# simple_eq_5532.net
KiCad netlist of a schematic drawn in EAGLE
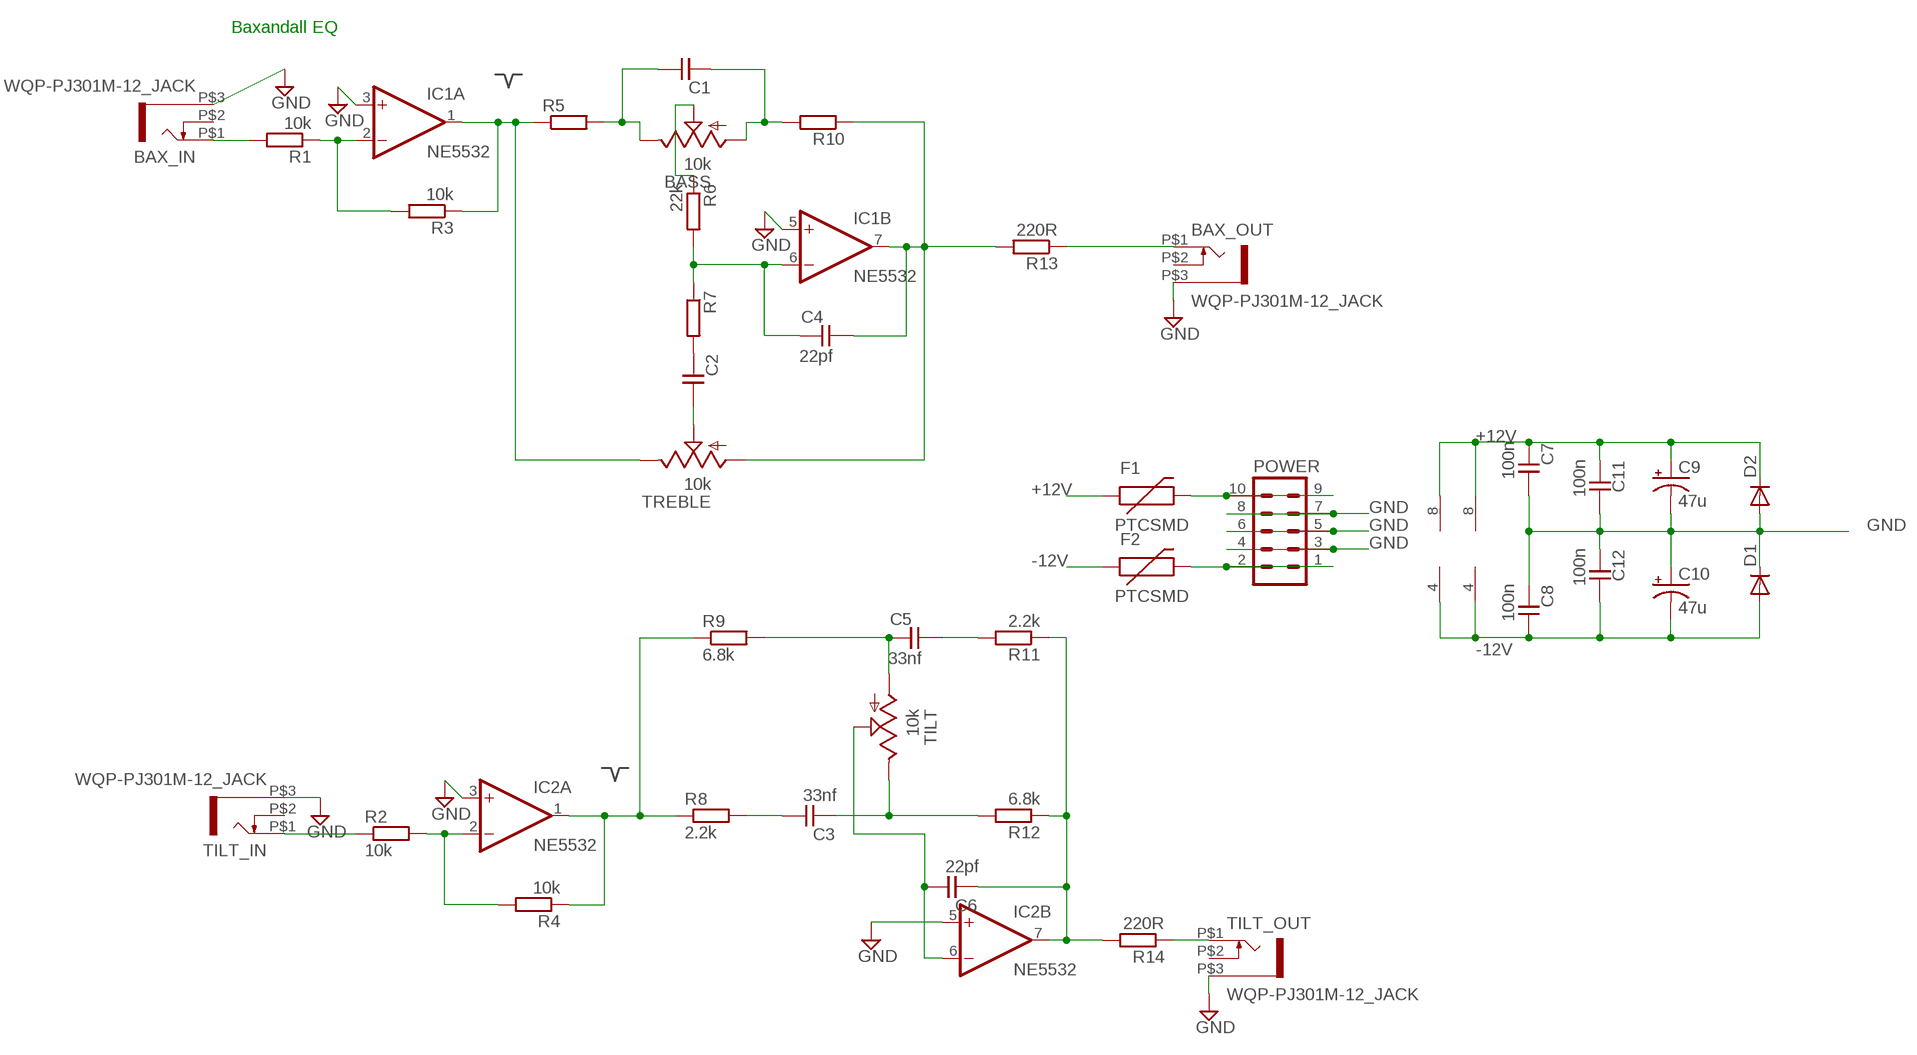
[diagram p0: schematic, sheet 1]

(export (version "E")
  (design (tool "Eeschema 10.0.6"))
  (components
    (comp (ref "BASS")
      (value "10k")
      (footprint "eagle-import:EVUF")
      (libsource (lib "eagle-import") (part "ALPHA-9MMAF2"))
    )
    (comp (ref "BAX_IN")
      (value "WQP-PJ301M-12_JACK")
      (footprint "eagle-import:WQP-PJ301M-12_JACK")
      (libsource (lib "eagle-import") (part "WQP-PJ301M-12_JACK"))
    )
    (comp (ref "BAX_OUT")
      (value "WQP-PJ301M-12_JACK")
      (footprint "eagle-import:WQP-PJ301M-12_JACK")
      (libsource (lib "eagle-import") (part "WQP-PJ301M-12_JACK"))
    )
    (comp (ref "C1")
      (value "C-EU0805_CAP")
      (footprint "eagle-import:R0805")
      (libsource (lib "eagle-import") (part "C-EU0805_CAP"))
    )
    (comp (ref "C2")
      (value "C-EU0805_CAP")
      (footprint "eagle-import:R0805")
      (libsource (lib "eagle-import") (part "C-EU0805_CAP"))
    )
    (comp (ref "C3")
      (value "33nf")
      (footprint "eagle-import:R0805")
      (libsource (lib "eagle-import") (part "C-EU0805_CAP"))
    )
    (comp (ref "C4")
      (value "22pf")
      (footprint "eagle-import:R0805")
      (libsource (lib "eagle-import") (part "C-EU0805_CAP"))
    )
    (comp (ref "C5")
      (value "33nf")
      (footprint "eagle-import:R0805")
      (libsource (lib "eagle-import") (part "C-EU0805_CAP"))
    )
    (comp (ref "C6")
      (value "22pf")
      (footprint "eagle-import:R0805")
      (libsource (lib "eagle-import") (part "C-EU0805_CAP"))
    )
    (comp (ref "C7")
      (value "100n")
      (footprint "eagle-import:R0805")
      (libsource (lib "eagle-import") (part "C-EU0805_CAP"))
    )
    (comp (ref "C8")
      (value "100n")
      (footprint "eagle-import:R0805")
      (libsource (lib "eagle-import") (part "C-EU0805_CAP"))
    )
    (comp (ref "C9")
      (value "47u")
      (footprint "eagle-import:PANASONIC_D")
      (libsource (lib "eagle-import") (part "CPOL-USD"))
    )
    (comp (ref "C10")
      (value "47u")
      (footprint "eagle-import:PANASONIC_D")
      (libsource (lib "eagle-import") (part "CPOL-USD"))
    )
    (comp (ref "C11")
      (value "100n")
      (footprint "eagle-import:R0805")
      (libsource (lib "eagle-import") (part "C-EU0805_CAP"))
    )
    (comp (ref "C12")
      (value "100n")
      (footprint "eagle-import:R0805")
      (libsource (lib "eagle-import") (part "C-EU0805_CAP"))
    )
    (comp (ref "D1")
      (value "DIODE-SOD123")
      (footprint "eagle-import:SOD123")
      (libsource (lib "eagle-import") (part "DIODE-SOD123"))
    )
    (comp (ref "D2")
      (value "DIODE-SOD123")
      (footprint "eagle-import:SOD123")
      (libsource (lib "eagle-import") (part "DIODE-SOD123"))
    )
    (comp (ref "F1")
      (value "PTCSMD")
      (footprint "eagle-import:PTC-1206")
      (libsource (lib "eagle-import") (part "PTCSMD"))
    )
    (comp (ref "F2")
      (value "PTCSMD")
      (footprint "eagle-import:PTC-1206")
      (libsource (lib "eagle-import") (part "PTCSMD"))
    )
    (comp (ref "IC1")
      (value "NE5532")
      (footprint "eagle-import:SO08")
      (libsource (lib "eagle-import") (part "TL072D"))
    )
    (comp (ref "IC2")
      (value "NE5532")
      (footprint "eagle-import:SO08")
      (libsource (lib "eagle-import") (part "TL072D"))
    )
    (comp (ref "POWER")
      (value "10_PIN_HEADER")
      (footprint "eagle-import:MA05-2")
      (libsource (lib "eagle-import") (part "10_PIN_HEADER"))
    )
    (comp (ref "R1")
      (value "10k")
      (footprint "eagle-import:R0805")
      (libsource (lib "eagle-import") (part "R-EU_R0805"))
    )
    (comp (ref "R2")
      (value "10k")
      (footprint "eagle-import:R0805")
      (libsource (lib "eagle-import") (part "R-EU_R0805"))
    )
    (comp (ref "R3")
      (value "10k")
      (footprint "eagle-import:R0805")
      (libsource (lib "eagle-import") (part "R-EU_R0805"))
    )
    (comp (ref "R4")
      (value "10k")
      (footprint "eagle-import:R0805")
      (libsource (lib "eagle-import") (part "R-EU_R0805"))
    )
    (comp (ref "R5")
      (value "R-EU_R0805")
      (footprint "eagle-import:R0805")
      (libsource (lib "eagle-import") (part "R-EU_R0805"))
    )
    (comp (ref "R6")
      (value "22k")
      (footprint "eagle-import:R0805")
      (libsource (lib "eagle-import") (part "R-EU_R0805"))
    )
    (comp (ref "R7")
      (value "R-EU_R0805")
      (footprint "eagle-import:R0805")
      (libsource (lib "eagle-import") (part "R-EU_R0805"))
    )
    (comp (ref "R8")
      (value "2.2k")
      (footprint "eagle-import:R0805")
      (libsource (lib "eagle-import") (part "R-EU_R0805"))
    )
    (comp (ref "R9")
      (value "6.8k")
      (footprint "eagle-import:R0805")
      (libsource (lib "eagle-import") (part "R-EU_R0805"))
    )
    (comp (ref "R10")
      (value "R-EU_R0805")
      (footprint "eagle-import:R0805")
      (libsource (lib "eagle-import") (part "R-EU_R0805"))
    )
    (comp (ref "R11")
      (value "2.2k")
      (footprint "eagle-import:R0805")
      (libsource (lib "eagle-import") (part "R-EU_R0805"))
    )
    (comp (ref "R12")
      (value "6.8k")
      (footprint "eagle-import:R0805")
      (libsource (lib "eagle-import") (part "R-EU_R0805"))
    )
    (comp (ref "R13")
      (value "220R")
      (footprint "eagle-import:R0805")
      (libsource (lib "eagle-import") (part "R-EU_R0805"))
    )
    (comp (ref "R14")
      (value "220R")
      (footprint "eagle-import:R0805")
      (libsource (lib "eagle-import") (part "R-EU_R0805"))
    )
    (comp (ref "TILT")
      (value "10k")
      (footprint "eagle-import:EVUF")
      (libsource (lib "eagle-import") (part "ALPHA-9MMAF2"))
    )
    (comp (ref "TILT_IN")
      (value "WQP-PJ301M-12_JACK")
      (footprint "eagle-import:WQP-PJ301M-12_JACK")
      (libsource (lib "eagle-import") (part "WQP-PJ301M-12_JACK"))
    )
    (comp (ref "TILT_OUT")
      (value "WQP-PJ301M-12_JACK")
      (footprint "eagle-import:WQP-PJ301M-12_JACK")
      (libsource (lib "eagle-import") (part "WQP-PJ301M-12_JACK"))
    )
    (comp (ref "TREBLE")
      (value "10k")
      (footprint "eagle-import:EVUF")
      (libsource (lib "eagle-import") (part "ALPHA-9MMAF2"))
    )
  )
  (nets
    (net (code "1") (name "/+12V") (class "Default")
      (node (ref "C11") (pin "2") (pinfunction "2_2") (pintype "passive"))
      (node (ref "C7") (pin "2") (pinfunction "2_2") (pintype "passive"))
      (node (ref "C9") (pin "+") (pinfunction "+_+") (pintype "passive"))
      (node (ref "D2") (pin "C") (pinfunction "C_C") (pintype "passive"))
      (node (ref "F1") (pin "1") (pinfunction "1_1") (pintype "bidirectional"))
      (node (ref "IC1") (pin "8") (pinfunction "V+_8") (pintype "power_in"))
      (node (ref "IC2") (pin "8") (pinfunction "V+_8") (pintype "power_in"))
    )
    (net (code "2") (name "/-12V") (class "Default")
      (node (ref "C10") (pin "-") (pinfunction "-_-") (pintype "passive"))
      (node (ref "C12") (pin "1") (pinfunction "1_1") (pintype "passive"))
      (node (ref "C8") (pin "1") (pinfunction "1_1") (pintype "passive"))
      (node (ref "D1") (pin "A") (pinfunction "A_A") (pintype "passive"))
      (node (ref "F2") (pin "1") (pinfunction "1_1") (pintype "bidirectional"))
      (node (ref "IC1") (pin "4") (pinfunction "V-_4") (pintype "power_in"))
      (node (ref "IC2") (pin "4") (pinfunction "V-_4") (pintype "power_in"))
    )
    (net (code "3") (name "GND") (class "Default")
      (node (ref "BAX_IN") (pin "P$3") (pinfunction "1_P$3") (pintype "passive"))
      (node (ref "BAX_OUT") (pin "P$3") (pinfunction "1_P$3") (pintype "passive"))
      (node (ref "C10") (pin "+") (pinfunction "+_+") (pintype "passive"))
      (node (ref "C11") (pin "1") (pinfunction "1_1") (pintype "passive"))
      (node (ref "C12") (pin "2") (pinfunction "2_2") (pintype "passive"))
      (node (ref "C7") (pin "1") (pinfunction "1_1") (pintype "passive"))
      (node (ref "C8") (pin "2") (pinfunction "2_2") (pintype "passive"))
      (node (ref "C9") (pin "-") (pinfunction "-_-") (pintype "passive"))
      (node (ref "D1") (pin "C") (pinfunction "C_C") (pintype "passive"))
      (node (ref "D2") (pin "A") (pinfunction "A_A") (pintype "passive"))
      (node (ref "IC1") (pin "3") (pinfunction "+IN_3") (pintype "input"))
      (node (ref "IC1") (pin "5") (pinfunction "+IN_5") (pintype "input"))
      (node (ref "IC2") (pin "3") (pinfunction "+IN_3") (pintype "input"))
      (node (ref "IC2") (pin "5") (pinfunction "+IN_5") (pintype "input"))
      (node (ref "POWER") (pin "3") (pinfunction "3_3") (pintype "passive"))
      (node (ref "POWER") (pin "4") (pinfunction "4_4") (pintype "passive"))
      (node (ref "POWER") (pin "5") (pinfunction "5_5") (pintype "passive"))
      (node (ref "POWER") (pin "6") (pinfunction "6_6") (pintype "passive"))
      (node (ref "POWER") (pin "7") (pinfunction "7_7") (pintype "passive"))
      (node (ref "POWER") (pin "8") (pinfunction "8_8") (pintype "passive"))
      (node (ref "TILT_IN") (pin "P$3") (pinfunction "1_P$3") (pintype "passive"))
      (node (ref "TILT_OUT") (pin "P$3") (pinfunction "1_P$3") (pintype "passive"))
    )
    (net (code "4") (name "Net-(BASS-A)") (class "Default")
      (node (ref "BASS") (pin "1") (pinfunction "A_1") (pintype "passive"))
      (node (ref "C1") (pin "2") (pinfunction "2_2") (pintype "passive"))
      (node (ref "R10") (pin "2") (pinfunction "2_2") (pintype "passive"))
    )
    (net (code "5") (name "Net-(BASS-E)") (class "Default")
      (node (ref "BASS") (pin "3") (pinfunction "E_3") (pintype "passive"))
      (node (ref "C1") (pin "1") (pinfunction "1_1") (pintype "passive"))
      (node (ref "R5") (pin "2") (pinfunction "2_2") (pintype "passive"))
    )
    (net (code "6") (name "Net-(BASS-S)") (class "Default")
      (node (ref "BASS") (pin "2") (pinfunction "S_2") (pintype "passive"))
      (node (ref "R6") (pin "1") (pinfunction "1_1") (pintype "passive"))
    )
    (net (code "7") (name "Net-(BAX_IN-2)") (class "Default")
      (node (ref "BAX_IN") (pin "P$1") (pinfunction "2_P$1") (pintype "passive"))
      (node (ref "R1") (pin "2") (pinfunction "2_2") (pintype "passive"))
    )
    (net (code "8") (name "Net-(BAX_OUT-2)") (class "Default")
      (node (ref "BAX_OUT") (pin "P$1") (pinfunction "2_P$1") (pintype "passive"))
      (node (ref "R13") (pin "1") (pinfunction "1_1") (pintype "passive"))
    )
    (net (code "9") (name "Net-(C2-Pad2)") (class "Default")
      (node (ref "C2") (pin "2") (pinfunction "2_2") (pintype "passive"))
      (node (ref "R7") (pin "2") (pinfunction "2_2") (pintype "passive"))
    )
    (net (code "10") (name "Net-(C3-Pad1)") (class "Default")
      (node (ref "C3") (pin "1") (pinfunction "1_1") (pintype "passive"))
      (node (ref "R8") (pin "2") (pinfunction "2_2") (pintype "passive"))
    )
    (net (code "11") (name "Net-(C5-Pad1)") (class "Default")
      (node (ref "C5") (pin "1") (pinfunction "1_1") (pintype "passive"))
      (node (ref "R11") (pin "2") (pinfunction "2_2") (pintype "passive"))
    )
    (net (code "12") (name "Net-(F1-Pad2)") (class "Default")
      (node (ref "F1") (pin "2") (pinfunction "2_2") (pintype "bidirectional"))
      (node (ref "POWER") (pin "10") (pinfunction "10_10") (pintype "passive"))
      (node (ref "POWER") (pin "9") (pinfunction "9_9") (pintype "passive"))
    )
    (net (code "13") (name "Net-(F2-Pad2)") (class "Default")
      (node (ref "F2") (pin "2") (pinfunction "2_2") (pintype "bidirectional"))
      (node (ref "POWER") (pin "1") (pinfunction "1_1") (pintype "passive"))
      (node (ref "POWER") (pin "2") (pinfunction "2_2") (pintype "passive"))
    )
    (net (code "14") (name "Net-(IC1A--IN)") (class "Default")
      (node (ref "IC1") (pin "2") (pinfunction "-IN_2") (pintype "input"))
      (node (ref "R1") (pin "1") (pinfunction "1_1") (pintype "passive"))
      (node (ref "R3") (pin "2") (pinfunction "2_2") (pintype "passive"))
    )
    (net (code "15") (name "Net-(IC1A-OUT)") (class "Default")
      (node (ref "IC1") (pin "1") (pinfunction "OUT_1") (pintype "output"))
      (node (ref "R3") (pin "1") (pinfunction "1_1") (pintype "passive"))
      (node (ref "R5") (pin "1") (pinfunction "1_1") (pintype "passive"))
      (node (ref "TREBLE") (pin "3") (pinfunction "E_3") (pintype "passive"))
    )
    (net (code "16") (name "Net-(IC1B--IN)") (class "Default")
      (node (ref "C4") (pin "2") (pinfunction "2_2") (pintype "passive"))
      (node (ref "IC1") (pin "6") (pinfunction "-IN_6") (pintype "input"))
      (node (ref "R6") (pin "2") (pinfunction "2_2") (pintype "passive"))
      (node (ref "R7") (pin "1") (pinfunction "1_1") (pintype "passive"))
    )
    (net (code "17") (name "Net-(IC1B-OUT)") (class "Default")
      (node (ref "C4") (pin "1") (pinfunction "1_1") (pintype "passive"))
      (node (ref "IC1") (pin "7") (pinfunction "OUT_7") (pintype "output"))
      (node (ref "R10") (pin "1") (pinfunction "1_1") (pintype "passive"))
      (node (ref "R13") (pin "2") (pinfunction "2_2") (pintype "passive"))
      (node (ref "TREBLE") (pin "1") (pinfunction "A_1") (pintype "passive"))
    )
    (net (code "18") (name "Net-(IC2A--IN)") (class "Default")
      (node (ref "IC2") (pin "2") (pinfunction "-IN_2") (pintype "input"))
      (node (ref "R2") (pin "2") (pinfunction "2_2") (pintype "passive"))
      (node (ref "R4") (pin "2") (pinfunction "2_2") (pintype "passive"))
    )
    (net (code "19") (name "Net-(IC2A-OUT)") (class "Default")
      (node (ref "IC2") (pin "1") (pinfunction "OUT_1") (pintype "output"))
      (node (ref "R4") (pin "1") (pinfunction "1_1") (pintype "passive"))
      (node (ref "R8") (pin "1") (pinfunction "1_1") (pintype "passive"))
      (node (ref "R9") (pin "1") (pinfunction "1_1") (pintype "passive"))
    )
    (net (code "20") (name "Net-(IC2B--IN)") (class "Default")
      (node (ref "C6") (pin "1") (pinfunction "1_1") (pintype "passive"))
      (node (ref "IC2") (pin "6") (pinfunction "-IN_6") (pintype "input"))
      (node (ref "TILT") (pin "2") (pinfunction "S_2") (pintype "passive"))
    )
    (net (code "21") (name "Net-(IC2B-OUT)") (class "Default")
      (node (ref "C6") (pin "2") (pinfunction "2_2") (pintype "passive"))
      (node (ref "IC2") (pin "7") (pinfunction "OUT_7") (pintype "output"))
      (node (ref "R11") (pin "1") (pinfunction "1_1") (pintype "passive"))
      (node (ref "R12") (pin "1") (pinfunction "1_1") (pintype "passive"))
      (node (ref "R14") (pin "2") (pinfunction "2_2") (pintype "passive"))
    )
    (net (code "22") (name "Net-(TILT-A)") (class "Default")
      (node (ref "C5") (pin "2") (pinfunction "2_2") (pintype "passive"))
      (node (ref "R9") (pin "2") (pinfunction "2_2") (pintype "passive"))
      (node (ref "TILT") (pin "1") (pinfunction "A_1") (pintype "passive"))
    )
    (net (code "23") (name "Net-(TILT-E)") (class "Default")
      (node (ref "C3") (pin "2") (pinfunction "2_2") (pintype "passive"))
      (node (ref "R12") (pin "2") (pinfunction "2_2") (pintype "passive"))
      (node (ref "TILT") (pin "3") (pinfunction "E_3") (pintype "passive"))
    )
    (net (code "24") (name "Net-(TILT_IN-2)") (class "Default")
      (node (ref "R2") (pin "1") (pinfunction "1_1") (pintype "passive"))
      (node (ref "TILT_IN") (pin "P$1") (pinfunction "2_P$1") (pintype "passive"))
    )
    (net (code "25") (name "Net-(TILT_OUT-2)") (class "Default")
      (node (ref "R14") (pin "1") (pinfunction "1_1") (pintype "passive"))
      (node (ref "TILT_OUT") (pin "P$1") (pinfunction "2_P$1") (pintype "passive"))
    )
    (net (code "26") (name "Net-(TREBLE-S)") (class "Default")
      (node (ref "C2") (pin "1") (pinfunction "1_1") (pintype "passive"))
      (node (ref "TREBLE") (pin "2") (pinfunction "S_2") (pintype "passive"))
    )
    (net (code "27") (name "unconnected-(BAX_IN-3-PadP$2)") (class "Default")
      (node (ref "BAX_IN") (pin "P$2") (pinfunction "3_P$2") (pintype "passive"))
    )
    (net (code "28") (name "unconnected-(BAX_OUT-3-PadP$2)") (class "Default")
      (node (ref "BAX_OUT") (pin "P$2") (pinfunction "3_P$2") (pintype "passive"))
    )
    (net (code "29") (name "unconnected-(TILT_IN-3-PadP$2)") (class "Default")
      (node (ref "TILT_IN") (pin "P$2") (pinfunction "3_P$2") (pintype "passive"))
    )
    (net (code "30") (name "unconnected-(TILT_OUT-3-PadP$2)") (class "Default")
      (node (ref "TILT_OUT") (pin "P$2") (pinfunction "3_P$2") (pintype "passive"))
    )
  )
)
